# MazeSolverSch.net
KiCad netlist of a schematic drawn in Altium Designer
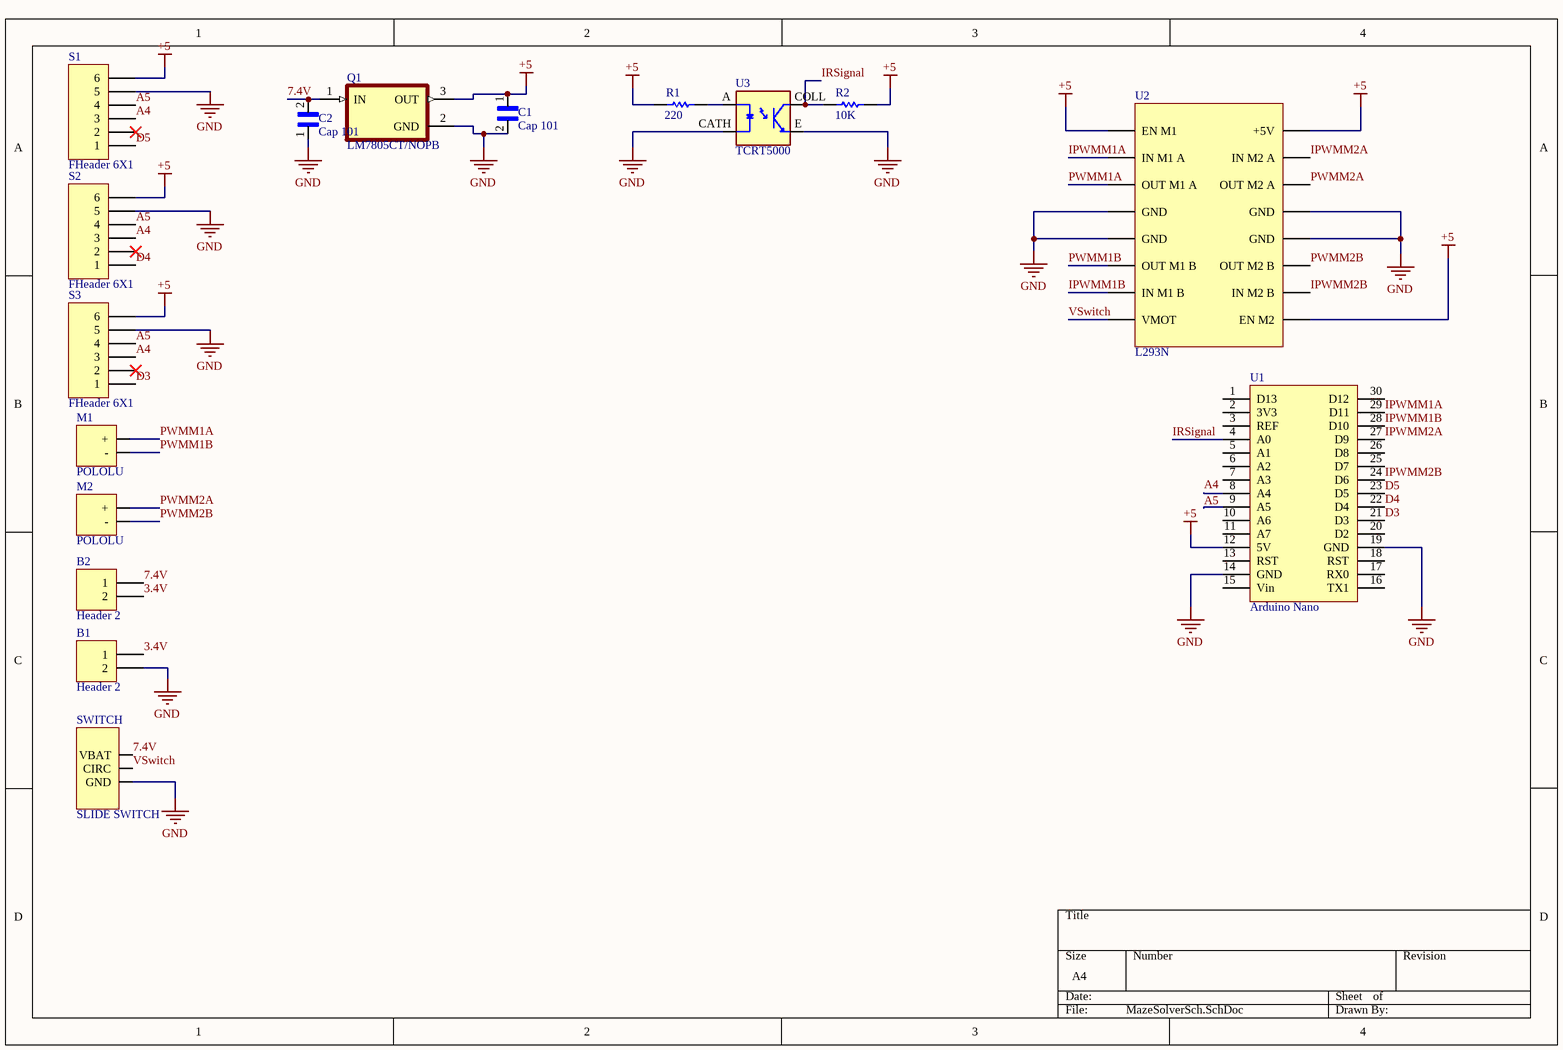
[diagram p0: MazeSolverSch.SchDoc]

(export (version "E")
  (design (tool "Eeschema 10.0.6"))
  (components
    (comp (ref "B1")
      (value "Header 2")
      (footprint "HDR1X2")
      (description "Header, 2-Pin")
      (fields (field (name "PUBLISHER") "Altium Limited"))
      (libsource (lib "LibreariasUniversalesMatuTorres") (part "Header 2"))
    )
    (comp (ref "B2")
      (value "Header 2")
      (footprint "HDR1X2")
      (description "Header, 2-Pin")
      (fields (field (name "PUBLISHER") "Altium Limited"))
      (libsource (lib "LibreariasUniversalesMatuTorres") (part "Header 2"))
    )
    (comp (ref "C1")
      (value "Cap 101")
      (footprint "LibreriasUniversalesMatuTorres:CAP_RCER71H224K1DBH03A")
      (description "CAP CER 4700PF 50V C0G/NP0 RAD")
      (fields (field (name "MP") "RCER71H224K1DBH03A"))
      (libsource (lib "") (part "RCER71H224K1DBH03A_1"))
    )
    (comp (ref "C2")
      (value "Cap 101")
      (footprint "LibreriasUniversalesMatuTorres:CAP_RCER71H224K1DBH03A")
      (description "CAP CER 4700PF 50V C0G/NP0 RAD")
      (fields (field (name "MP") "RCER71H224K1DBH03A"))
      (libsource (lib "LibreariasUniversalesMatuTorres") (part "RCER71H224K1DBH03A"))
    )
    (comp (ref "M1")
      (value "POLOLU")
      (footprint "MOTOR")
      (fields (field (name "PUBLISHER") "Altium Limited"))
      (libsource (lib "LibreariasUniversalesMatuTorres") (part "POLOLU"))
    )
    (comp (ref "M2")
      (value "POLOLU")
      (footprint "MOTOR")
      (fields (field (name "PUBLISHER") "Altium Limited"))
      (libsource (lib "LibreariasUniversalesMatuTorres") (part "POLOLU"))
    )
    (comp (ref "Q1")
      (value "LM7805CT/NOPB")
      (footprint "TO254P1054X470X2600-3")
      (description "Linear Voltage Regulator IC Positive Fixed 1 Output 1.5A TO-220-3")
      (fields (field (name "MF") "ON Semiconductor") (field (name "MP") "LM7805CT"))
      (libsource (lib "LibreariasUniversalesMatuTorres") (part "LM7805CT/NOPB"))
    )
    (comp (ref "R1")
      (value "220")
      (footprint "Res1")
      (description "Resistor")
      (fields (field (name "PUBLISHER") "Altium Limited"))
      (libsource (lib "LibreariasUniversalesMatuTorres") (part "Res1"))
    )
    (comp (ref "R2")
      (value "10K")
      (footprint "Res1")
      (description "Resistor")
      (fields (field (name "PUBLISHER") "Altium Limited"))
      (libsource (lib "LibreariasUniversalesMatuTorres") (part "Res1"))
    )
    (comp (ref "S1")
      (value "FHeader 6X1")
      (footprint "FHDR1X6")
      (fields (field (name "PUBLISHER") "Altium Limited"))
      (libsource (lib "LibreariasUniversalesMatuTorres") (part "FHeader 6X1"))
    )
    (comp (ref "S2")
      (value "FHeader 6X1")
      (footprint "FHDR1X6")
      (fields (field (name "PUBLISHER") "Altium Limited"))
      (libsource (lib "LibreariasUniversalesMatuTorres") (part "FHeader 6X1"))
    )
    (comp (ref "S3")
      (value "FHeader 6X1")
      (footprint "FHDR1X6")
      (fields (field (name "PUBLISHER") "Altium Limited"))
      (libsource (lib "LibreariasUniversalesMatuTorres") (part "FHeader 6X1"))
    )
    (comp (ref "SWITCH")
      (value "SLIDE SWITCH")
      (footprint "Slide Switch")
      (libsource (lib "LibreariasUniversalesMatuTorres") (part "SLIDE SWITCH"))
    )
    (comp (ref "U1")
      (value "Arduino Nano")
      (footprint "Arduino nano")
      (libsource (lib "LibreariasUniversalesMatuTorres") (part "ARDUINO NANO"))
    )
    (comp (ref "U2")
      (value "L293N")
      (footprint "L293N")
      (fields (field (name "PUBLISHER") "Altium Limited"))
      (libsource (lib "LibreariasUniversalesMatuTorres") (part "L293N"))
    )
    (comp (ref "U3")
      (value "TCRT5000")
      (footprint "LibreriasUniversalesMatuTorres:OPTO_TCRT5000")
      (description "950 nm 60 mA Through Hole Reflective Optical Sensor with Transistor Output")
      (libsource (lib "LibreariasUniversalesMatuTorres") (part "TCRT5000"))
    )
  )
  (nets
    (net (code "1") (name "+5") (class "Default")
      (node (ref "C1") (pin "1") (pinfunction "1_1") (pintype "passive"))
      (node (ref "Q1") (pin "3") (pinfunction "OUT_3") (pintype "output"))
      (node (ref "R1") (pin "1") (pinfunction "1_1") (pintype "passive"))
      (node (ref "R2") (pin "2") (pinfunction "2_2") (pintype "passive"))
      (node (ref "S1") (pin "6") (pinfunction "6_6") (pintype "passive"))
      (node (ref "S2") (pin "6") (pinfunction "6_6") (pintype "passive"))
      (node (ref "S3") (pin "6") (pinfunction "6_6") (pintype "passive"))
      (node (ref "U1") (pin "12") (pinfunction "5V_12") (pintype "passive"))
      (node (ref "U2") (pin "1") (pinfunction "EN_M1_1") (pintype "passive"))
      (node (ref "U2") (pin "16") (pinfunction "+5V_16") (pintype "passive"))
      (node (ref "U2") (pin "9") (pinfunction "EN_M2_9") (pintype "passive"))
    )
    (net (code "2") (name "/3.4V") (class "Default")
      (node (ref "B1") (pin "1") (pinfunction "1_1") (pintype "passive"))
      (node (ref "B2") (pin "2") (pinfunction "2_2") (pintype "passive"))
    )
    (net (code "3") (name "/7.4V") (class "Default")
      (node (ref "B2") (pin "1") (pinfunction "1_1") (pintype "passive"))
      (node (ref "C2") (pin "2") (pinfunction "2_2") (pintype "passive"))
      (node (ref "Q1") (pin "1") (pinfunction "IN_1") (pintype "input"))
      (node (ref "SWITCH") (pin "0") (pinfunction "VBAT_0") (pintype "passive"))
    )
    (net (code "4") (name "/A4") (class "Default")
      (node (ref "S1") (pin "3") (pinfunction "3_3") (pintype "passive"))
      (node (ref "S2") (pin "3") (pinfunction "3_3") (pintype "passive"))
      (node (ref "S3") (pin "3") (pinfunction "3_3") (pintype "passive"))
      (node (ref "U1") (pin "8") (pinfunction "A4_8") (pintype "passive"))
    )
    (net (code "5") (name "/A5") (class "Default")
      (node (ref "S1") (pin "4") (pinfunction "4_4") (pintype "passive"))
      (node (ref "S2") (pin "4") (pinfunction "4_4") (pintype "passive"))
      (node (ref "S3") (pin "4") (pinfunction "4_4") (pintype "passive"))
      (node (ref "U1") (pin "9") (pinfunction "A5_9") (pintype "passive"))
    )
    (net (code "6") (name "/D3") (class "Default")
      (node (ref "S3") (pin "1") (pinfunction "1_1") (pintype "passive"))
      (node (ref "U1") (pin "21") (pinfunction "D3_21") (pintype "passive"))
    )
    (net (code "7") (name "/D4") (class "Default")
      (node (ref "S2") (pin "1") (pinfunction "1_1") (pintype "passive"))
      (node (ref "U1") (pin "22") (pinfunction "D4_22") (pintype "passive"))
    )
    (net (code "8") (name "/D5") (class "Default")
      (node (ref "S1") (pin "1") (pinfunction "1_1") (pintype "passive"))
      (node (ref "U1") (pin "23") (pinfunction "D5_23") (pintype "passive"))
    )
    (net (code "9") (name "/IPWMM1A") (class "Default")
      (node (ref "U1") (pin "29") (pinfunction "D11_29") (pintype "passive"))
      (node (ref "U2") (pin "2") (pinfunction "IN_M1_A_2") (pintype "passive"))
    )
    (net (code "10") (name "/IPWMM1B") (class "Default")
      (node (ref "U1") (pin "28") (pinfunction "D10_28") (pintype "passive"))
      (node (ref "U2") (pin "7") (pinfunction "IN_M1_B_7") (pintype "passive"))
    )
    (net (code "11") (name "/IPWMM2A") (class "Default")
      (node (ref "U1") (pin "27") (pinfunction "D9_27") (pintype "passive"))
      (node (ref "U2") (pin "15") (pinfunction "IN_M2_A_15") (pintype "passive"))
    )
    (net (code "12") (name "/IPWMM2B") (class "Default")
      (node (ref "U1") (pin "24") (pinfunction "D6_24") (pintype "passive"))
      (node (ref "U2") (pin "10") (pinfunction "IN_M2_B_10") (pintype "passive"))
    )
    (net (code "13") (name "/IRSignal") (class "Default")
      (node (ref "R2") (pin "1") (pinfunction "1_1") (pintype "passive"))
      (node (ref "U1") (pin "4") (pinfunction "A0_4") (pintype "passive"))
      (node (ref "U3") (pin "COLL") (pinfunction "COLL_COLL") (pintype "passive"))
    )
    (net (code "14") (name "/PWMM1A") (class "Default")
      (node (ref "M1") (pin "+") (pinfunction "+_+") (pintype "passive"))
      (node (ref "U2") (pin "3") (pinfunction "OUT_M1_A_3") (pintype "passive"))
    )
    (net (code "15") (name "/PWMM1B") (class "Default")
      (node (ref "M1") (pin "-") (pinfunction "-_-") (pintype "passive"))
      (node (ref "U2") (pin "6") (pinfunction "OUT_M1_B_6") (pintype "passive"))
    )
    (net (code "16") (name "/PWMM2A") (class "Default")
      (node (ref "M2") (pin "+") (pinfunction "+_+") (pintype "passive"))
      (node (ref "U2") (pin "14") (pinfunction "OUT_M2_A_14") (pintype "passive"))
    )
    (net (code "17") (name "/PWMM2B") (class "Default")
      (node (ref "M2") (pin "-") (pinfunction "-_-") (pintype "passive"))
      (node (ref "U2") (pin "11") (pinfunction "OUT_M2_B_11") (pintype "passive"))
    )
    (net (code "18") (name "/VSwitch") (class "Default")
      (node (ref "SWITCH") (pin "1") (pinfunction "CIRC_1") (pintype "passive"))
      (node (ref "U2") (pin "8") (pinfunction "VMOT_8") (pintype "passive"))
    )
    (net (code "19") (name "GND") (class "Default")
      (node (ref "B1") (pin "2") (pinfunction "2_2") (pintype "passive"))
      (node (ref "C1") (pin "2") (pinfunction "2_2") (pintype "passive"))
      (node (ref "C2") (pin "1") (pinfunction "1_1") (pintype "passive"))
      (node (ref "Q1") (pin "2") (pinfunction "GND_2") (pintype "power_in"))
      (node (ref "S1") (pin "5") (pinfunction "5_5") (pintype "passive"))
      (node (ref "S2") (pin "5") (pinfunction "5_5") (pintype "passive"))
      (node (ref "S3") (pin "5") (pinfunction "5_5") (pintype "passive"))
      (node (ref "SWITCH") (pin "2") (pinfunction "GND_2") (pintype "passive"))
      (node (ref "U1") (pin "14") (pinfunction "GND_14") (pintype "passive"))
      (node (ref "U1") (pin "19") (pinfunction "GND_19") (pintype "passive"))
      (node (ref "U2") (pin "12") (pinfunction "GND_12") (pintype "passive"))
      (node (ref "U2") (pin "13") (pinfunction "GND_13") (pintype "passive"))
      (node (ref "U2") (pin "4") (pinfunction "GND_4") (pintype "passive"))
      (node (ref "U2") (pin "5") (pinfunction "GND_5") (pintype "passive"))
      (node (ref "U3") (pin "CATH") (pinfunction "CATH_CATH") (pintype "passive"))
      (node (ref "U3") (pin "E") (pinfunction "E_E") (pintype "passive"))
    )
    (net (code "20") (name "Net-(R1-Pad2)") (class "Default")
      (node (ref "R1") (pin "2") (pinfunction "2_2") (pintype "passive"))
      (node (ref "U3") (pin "A") (pinfunction "A_A") (pintype "passive"))
    )
    (net (code "21") (name "unconnected-(S1-Pad2)") (class "Default")
      (node (ref "S1") (pin "2") (pinfunction "2_2") (pintype "passive+no_connect"))
    )
    (net (code "22") (name "unconnected-(S2-Pad2)") (class "Default")
      (node (ref "S2") (pin "2") (pinfunction "2_2") (pintype "passive+no_connect"))
    )
    (net (code "23") (name "unconnected-(S3-Pad2)") (class "Default")
      (node (ref "S3") (pin "2") (pinfunction "2_2") (pintype "passive+no_connect"))
    )
    (net (code "24") (name "unconnected-(U1-3V3-Pad2)") (class "Default")
      (node (ref "U1") (pin "2") (pinfunction "3V3_2") (pintype "passive"))
    )
    (net (code "25") (name "unconnected-(U1-A1-Pad5)") (class "Default")
      (node (ref "U1") (pin "5") (pinfunction "A1_5") (pintype "passive"))
    )
    (net (code "26") (name "unconnected-(U1-A2-Pad6)") (class "Default")
      (node (ref "U1") (pin "6") (pinfunction "A2_6") (pintype "passive"))
    )
    (net (code "27") (name "unconnected-(U1-A3-Pad7)") (class "Default")
      (node (ref "U1") (pin "7") (pinfunction "A3_7") (pintype "passive"))
    )
    (net (code "28") (name "unconnected-(U1-A6-Pad10)") (class "Default")
      (node (ref "U1") (pin "10") (pinfunction "A6_10") (pintype "passive"))
    )
    (net (code "29") (name "unconnected-(U1-A7-Pad11)") (class "Default")
      (node (ref "U1") (pin "11") (pinfunction "A7_11") (pintype "passive"))
    )
    (net (code "30") (name "unconnected-(U1-D2-Pad20)") (class "Default")
      (node (ref "U1") (pin "20") (pinfunction "D2_20") (pintype "passive"))
    )
    (net (code "31") (name "unconnected-(U1-D7-Pad25)") (class "Default")
      (node (ref "U1") (pin "25") (pinfunction "D7_25") (pintype "passive"))
    )
    (net (code "32") (name "unconnected-(U1-D8-Pad26)") (class "Default")
      (node (ref "U1") (pin "26") (pinfunction "D8_26") (pintype "passive"))
    )
    (net (code "33") (name "unconnected-(U1-D12-Pad30)") (class "Default")
      (node (ref "U1") (pin "30") (pinfunction "D12_30") (pintype "passive"))
    )
    (net (code "34") (name "unconnected-(U1-D13-Pad1)") (class "Default")
      (node (ref "U1") (pin "1") (pinfunction "D13_1") (pintype "passive"))
    )
    (net (code "35") (name "unconnected-(U1-REF-Pad3)") (class "Default")
      (node (ref "U1") (pin "3") (pinfunction "REF_3") (pintype "passive"))
    )
    (net (code "36") (name "unconnected-(U1-RST-Pad13)") (class "Default")
      (node (ref "U1") (pin "13") (pinfunction "RST_13") (pintype "passive"))
    )
    (net (code "37") (name "unconnected-(U1-RST-Pad18)") (class "Default")
      (node (ref "U1") (pin "18") (pinfunction "RST_18") (pintype "passive"))
    )
    (net (code "38") (name "unconnected-(U1-RX0-Pad17)") (class "Default")
      (node (ref "U1") (pin "17") (pinfunction "RX0_17") (pintype "passive"))
    )
    (net (code "39") (name "unconnected-(U1-TX1-Pad16)") (class "Default")
      (node (ref "U1") (pin "16") (pinfunction "TX1_16") (pintype "passive"))
    )
    (net (code "40") (name "unconnected-(U1-Vin-Pad15)") (class "Default")
      (node (ref "U1") (pin "15") (pinfunction "Vin_15") (pintype "passive"))
    )
  )
)
